# 5AC-DC.net
KiCad netlist of a schematic drawn in EAGLE
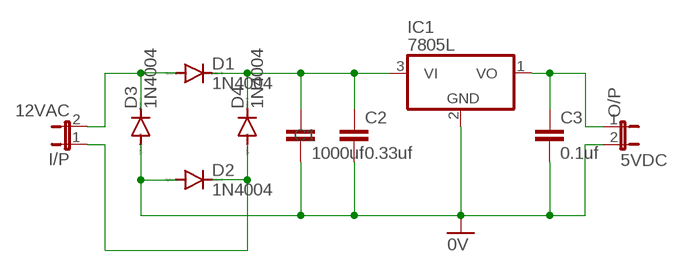
[diagram p0: schematic, sheet 1]

(export (version "E")
  (design (tool "Eeschema 10.0.6"))
  (components
    (comp (ref "C1")
      (value "1000uf")
      (footprint "eagle-import:C2.5-3")
      (libsource (lib "eagle-import") (part "C2,5-3"))
    )
    (comp (ref "C2")
      (value "0.33uf")
      (footprint "eagle-import:C2.5-3")
      (libsource (lib "eagle-import") (part "C2,5-3"))
    )
    (comp (ref "C3")
      (value "0.1uf")
      (footprint "eagle-import:C2.5-3")
      (libsource (lib "eagle-import") (part "C2,5-3"))
    )
    (comp (ref "D1")
      (value "1N4004")
      (footprint "eagle-import:DO41-10")
      (libsource (lib "eagle-import") (part "1N4004"))
    )
    (comp (ref "D2")
      (value "1N4004")
      (footprint "eagle-import:DO41-10")
      (libsource (lib "eagle-import") (part "1N4004"))
    )
    (comp (ref "D3")
      (value "1N4004")
      (footprint "eagle-import:DO41-10")
      (libsource (lib "eagle-import") (part "1N4004"))
    )
    (comp (ref "D4")
      (value "1N4004")
      (footprint "eagle-import:DO41-10")
      (libsource (lib "eagle-import") (part "1N4004"))
    )
    (comp (ref "I/P")
      (value "12VAC")
      (footprint "eagle-import:JP1")
      (libsource (lib "eagle-import") (part "JP1E"))
    )
    (comp (ref "IC1")
      (value "7805L")
      (footprint "eagle-import:TO92")
      (libsource (lib "eagle-import") (part "78L05"))
    )
    (comp (ref "O/P")
      (value "5VDC")
      (footprint "eagle-import:JP1")
      (libsource (lib "eagle-import") (part "JP1E"))
    )
  )
  (nets
    (net (code "1") (name "0V") (class "Default")
      (node (ref "C1") (pin "2") (pinfunction "2_2") (pintype "passive"))
      (node (ref "C2") (pin "2") (pinfunction "2_2") (pintype "passive"))
      (node (ref "C3") (pin "2") (pinfunction "2_2") (pintype "passive"))
      (node (ref "D2") (pin "A") (pinfunction "A_A") (pintype "passive"))
      (node (ref "D3") (pin "A") (pinfunction "A_A") (pintype "passive"))
      (node (ref "IC1") (pin "2") (pinfunction "GND_2") (pintype "passive"))
      (node (ref "O/P") (pin "2") (pinfunction "2_2") (pintype "passive"))
    )
    (net (code "2") (name "Net-(D1-PadA)") (class "Default")
      (node (ref "D1") (pin "A") (pinfunction "A_A") (pintype "passive"))
      (node (ref "D3") (pin "C") (pinfunction "C_C") (pintype "passive"))
      (node (ref "I/P") (pin "2") (pinfunction "2_2") (pintype "passive"))
    )
    (net (code "3") (name "Net-(D2-PadC)") (class "Default")
      (node (ref "D2") (pin "C") (pinfunction "C_C") (pintype "passive"))
      (node (ref "D4") (pin "A") (pinfunction "A_A") (pintype "passive"))
      (node (ref "I/P") (pin "1") (pinfunction "1_1") (pintype "passive"))
    )
    (net (code "4") (name "Net-(IC1-VI)") (class "Default")
      (node (ref "C1") (pin "1") (pinfunction "1_1") (pintype "passive"))
      (node (ref "C2") (pin "1") (pinfunction "1_1") (pintype "passive"))
      (node (ref "D1") (pin "C") (pinfunction "C_C") (pintype "passive"))
      (node (ref "D4") (pin "C") (pinfunction "C_C") (pintype "passive"))
      (node (ref "IC1") (pin "3") (pinfunction "VI_3") (pintype "input"))
    )
    (net (code "5") (name "Net-(IC1-VO)") (class "Default")
      (node (ref "C3") (pin "1") (pinfunction "1_1") (pintype "passive"))
      (node (ref "IC1") (pin "1") (pinfunction "VO_1") (pintype "passive"))
      (node (ref "O/P") (pin "1") (pinfunction "1_1") (pintype "passive"))
    )
  )
)
